# Sensors.net
KiCad netlist of a schematic drawn in Altium Designer
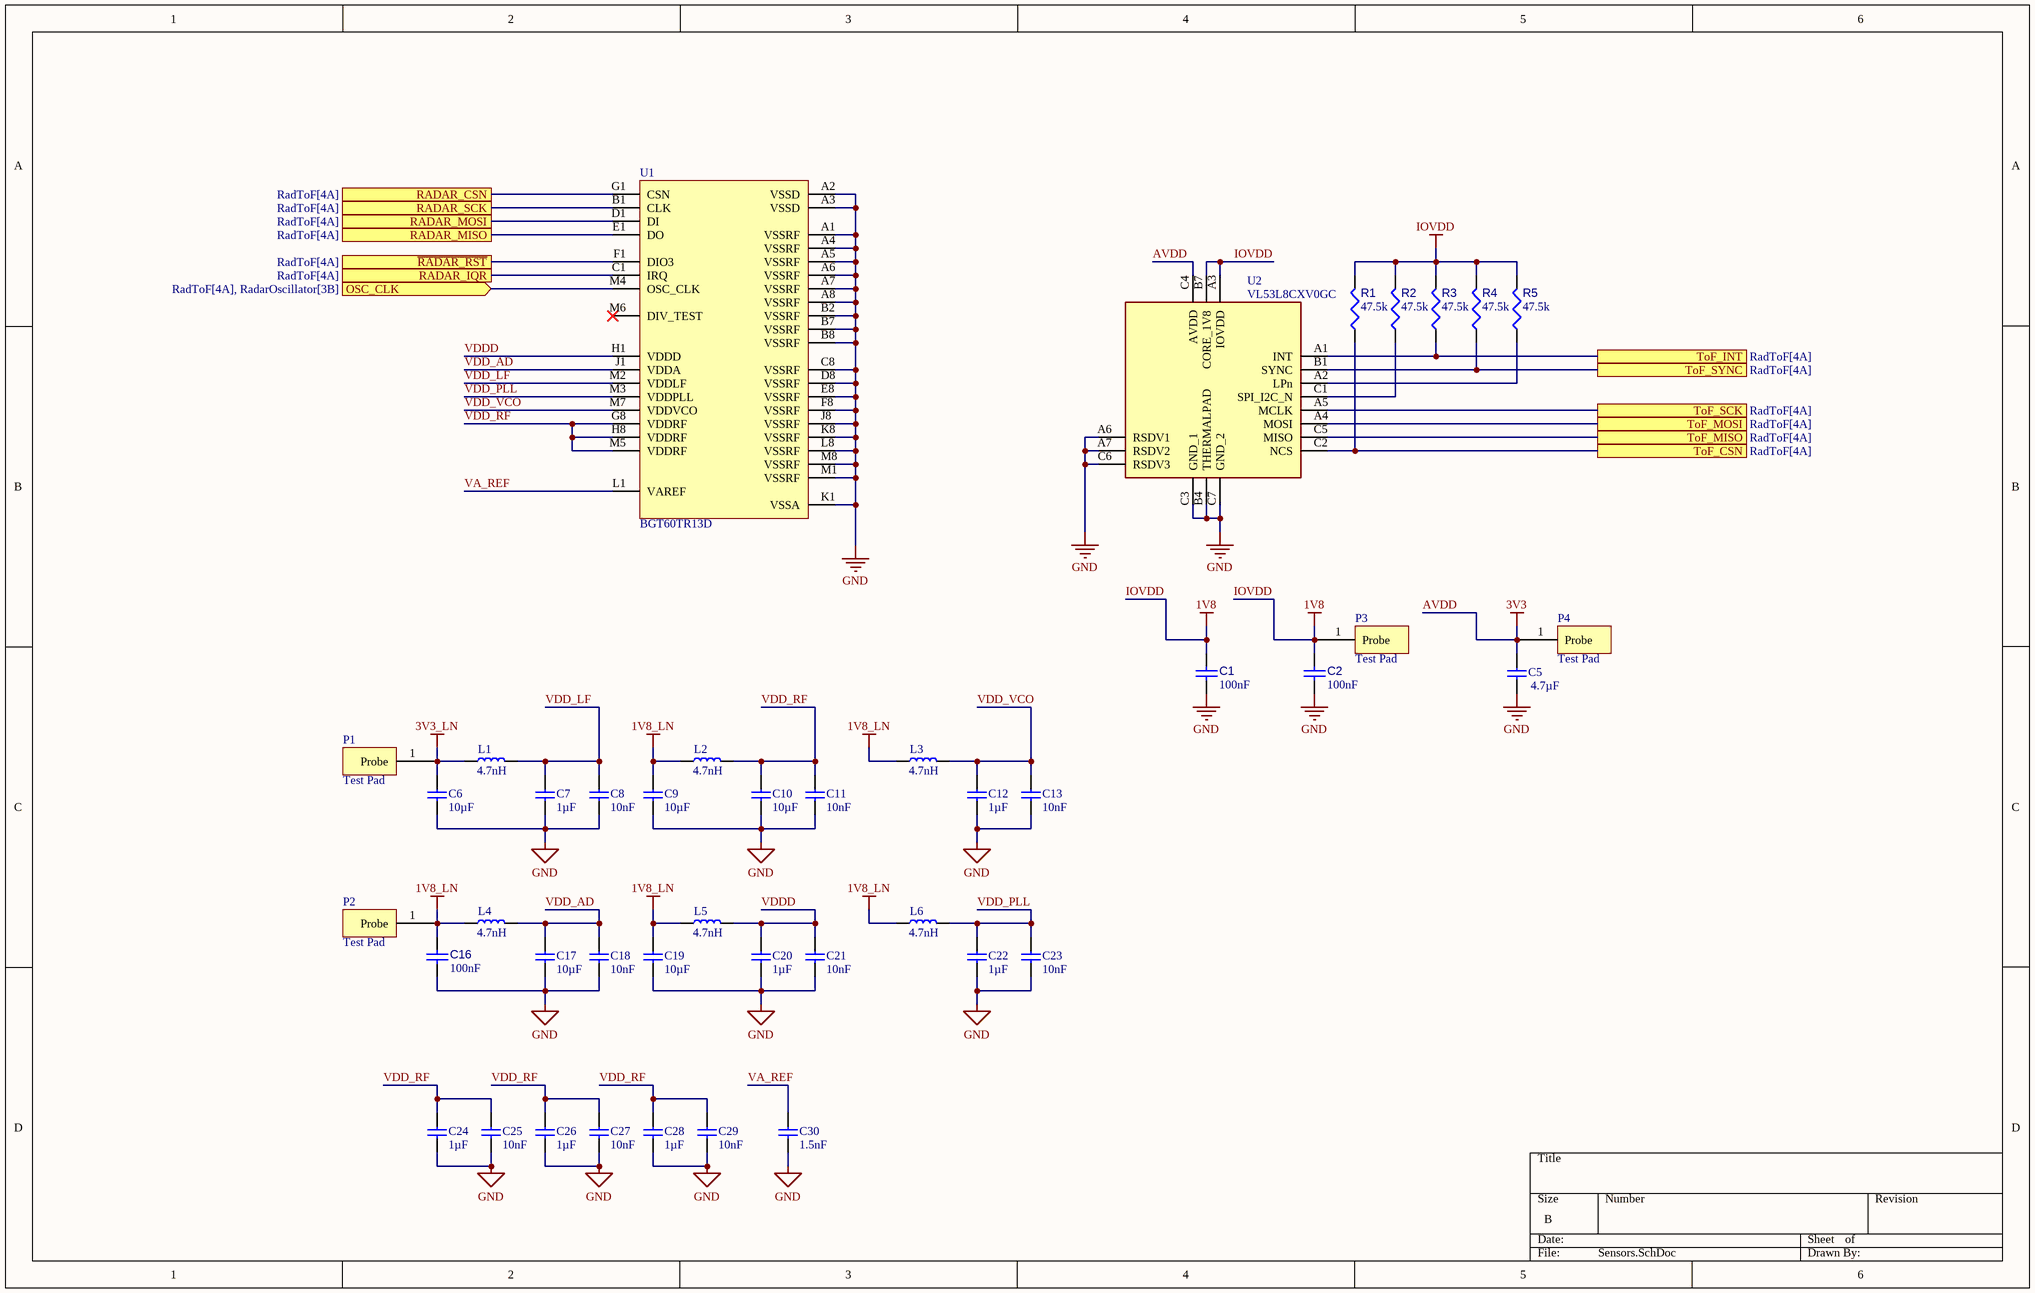
[diagram p0: Sensors.SchDoc]

(export (version "E")
  (design (tool "Eeschema 10.0.6"))
  (components
    (comp (ref "C1")
      (value "100nF")
      (footprint "CAPC0402(1005)60_L")
      (description "Chip Capacitor, 100nF +/-20%, 50V, 0402, Thickness 0.6 mm")
      (fields (field (name "TOLERANCE") "10%") (field (name "Comment") "Capacitor 100nF +/-20% 50V 0402"))
      (libsource (lib "Patrick Hupertz") (part "CAP-NP-2"))
    )
    (comp (ref "C2")
      (value "100nF")
      (footprint "CAPC0402(1005)60_L")
      (description "Chip Capacitor, 100nF +/-20%, 50V, 0402, Thickness 0.6 mm")
      (fields (field (name "TOLERANCE") "10%") (field (name "Comment") "Capacitor 100nF +/-20% 50V 0402"))
      (libsource (lib "Patrick Hupertz") (part "CAP-NP-2"))
    )
    (comp (ref "C5")
      (value "4.7µF")
      (footprint "CAP0201")
      (description "CAP CER  4.7uF 6.3V X5R 0201")
      (fields
        (field (name "TOLERANCE") "20%")
        (field (name "MANUFACTURER PART NUMBER") "GRM035R60J475ME15D")
        (field (name "SOURCE") "schuluka.SchLib")
      )
      (libsource (lib "Patrick Hupertz") (part "C_GRT033C80J224KE01D"))
    )
    (comp (ref "C6")
      (value "10µF")
      (footprint "CAP0402")
      (description "CAP CER  10uF 10V X5R 20% 0402")
      (fields
        (field (name "MANUFACTURER") "Murata Electronics")
        (field (name "TOLERANCE") "5%")
        (field (name "SOURCE") "schuluka.SchLib")
      )
      (libsource (lib "Patrick Hupertz") (part "C_GRT033C80J224KE01D"))
    )
    (comp (ref "C7")
      (value "1µF")
      (footprint "CAP0402")
      (description "CAP CER 1uF 25V X5R 0402")
      (fields
        (field (name "MANUFACTURER PART NUMBER") "GRM033R61A105ME15D")
        (field (name "MANUFACTURER") "Murata")
        (field (name "SOURCE") "schuluka.SchLib")
      )
      (libsource (lib "Patrick Hupertz") (part "C_GRT033C80J224KE01D"))
    )
    (comp (ref "C8")
      (value "10nF")
      (footprint "CAP0201")
      (description "CAP CER 10nF 6.3V X7R 0201")
      (fields
        (field (name "MANUFACTURER") "Murata Electronics")
        (field (name "TOLERANCE") "5%")
        (field (name "SOURCE") "schuluka.SchLib")
      )
      (libsource (lib "Patrick Hupertz") (part "C_GRT033C80J224KE01D"))
    )
    (comp (ref "C9")
      (value "10µF")
      (footprint "CAP0402")
      (description "CAP CER  10uF 10V X5R 20% 0402")
      (fields
        (field (name "MANUFACTURER") "Murata Electronics")
        (field (name "TOLERANCE") "5%")
        (field (name "SOURCE") "schuluka.SchLib")
      )
      (libsource (lib "Patrick Hupertz") (part "C_GRT033C80J224KE01D"))
    )
    (comp (ref "C10")
      (value "10µF")
      (footprint "CAP0402")
      (description "CAP CER  10uF 10V X5R 20% 0402")
      (fields
        (field (name "MANUFACTURER") "Murata Electronics")
        (field (name "TOLERANCE") "5%")
        (field (name "SOURCE") "schuluka.SchLib")
      )
      (libsource (lib "Patrick Hupertz") (part "C_GRT033C80J224KE01D"))
    )
    (comp (ref "C11")
      (value "10nF")
      (footprint "CAP0201")
      (description "CAP CER 10nF 6.3V X7R 0201")
      (fields
        (field (name "MANUFACTURER") "Murata Electronics")
        (field (name "TOLERANCE") "5%")
        (field (name "SOURCE") "schuluka.SchLib")
      )
      (libsource (lib "Patrick Hupertz") (part "C_GRT033C80J224KE01D"))
    )
    (comp (ref "C12")
      (value "1µF")
      (footprint "CAP0402")
      (description "CAP CER 1uF 25V X5R 0402")
      (fields
        (field (name "MANUFACTURER PART NUMBER") "GRM033R61A105ME15D")
        (field (name "MANUFACTURER") "Murata")
        (field (name "SOURCE") "schuluka.SchLib")
      )
      (libsource (lib "Patrick Hupertz") (part "C_GRT033C80J224KE01D"))
    )
    (comp (ref "C13")
      (value "10nF")
      (footprint "CAP0201")
      (description "CAP CER 10nF 6.3V X7R 0201")
      (fields
        (field (name "MANUFACTURER") "Murata Electronics")
        (field (name "TOLERANCE") "5%")
        (field (name "SOURCE") "schuluka.SchLib")
      )
      (libsource (lib "Patrick Hupertz") (part "C_GRT033C80J224KE01D"))
    )
    (comp (ref "C16")
      (value "100nF")
      (footprint "CAPC0402(1005)60_L")
      (description "Chip Capacitor, 100nF +/-20%, 50V, 0402, Thickness 0.6 mm")
      (fields (field (name "TOLERANCE") "10%") (field (name "Comment") "Capacitor 100nF +/-20% 50V 0402"))
      (libsource (lib "Patrick Hupertz") (part "CAP-NP-2"))
    )
    (comp (ref "C17")
      (value "10µF")
      (footprint "CAP0402")
      (description "CAP CER  10uF 10V X5R 20% 0402")
      (fields
        (field (name "MANUFACTURER") "Murata Electronics")
        (field (name "TOLERANCE") "5%")
        (field (name "SOURCE") "schuluka.SchLib")
      )
      (libsource (lib "Patrick Hupertz") (part "C_GRT033C80J224KE01D"))
    )
    (comp (ref "C18")
      (value "10nF")
      (footprint "CAP0201")
      (description "CAP CER 10nF 6.3V X7R 0201")
      (fields
        (field (name "MANUFACTURER") "Murata Electronics")
        (field (name "TOLERANCE") "5%")
        (field (name "SOURCE") "schuluka.SchLib")
      )
      (libsource (lib "Patrick Hupertz") (part "C_GRT033C80J224KE01D"))
    )
    (comp (ref "C19")
      (value "10µF")
      (footprint "CAP0402")
      (description "CAP CER  10uF 10V X5R 20% 0402")
      (fields
        (field (name "MANUFACTURER") "Murata Electronics")
        (field (name "TOLERANCE") "5%")
        (field (name "SOURCE") "schuluka.SchLib")
      )
      (libsource (lib "Patrick Hupertz") (part "C_GRT033C80J224KE01D"))
    )
    (comp (ref "C20")
      (value "1µF")
      (footprint "CAP0402")
      (description "CAP CER 1uF 25V X5R 0402")
      (fields
        (field (name "MANUFACTURER PART NUMBER") "GRM033R61A105ME15D")
        (field (name "MANUFACTURER") "Murata")
        (field (name "SOURCE") "schuluka.SchLib")
      )
      (libsource (lib "Patrick Hupertz") (part "C_GRT033C80J224KE01D"))
    )
    (comp (ref "C21")
      (value "10nF")
      (footprint "CAP0201")
      (description "CAP CER 10nF 6.3V X7R 0201")
      (fields
        (field (name "MANUFACTURER") "Murata Electronics")
        (field (name "TOLERANCE") "5%")
        (field (name "SOURCE") "schuluka.SchLib")
      )
      (libsource (lib "Patrick Hupertz") (part "C_GRT033C80J224KE01D"))
    )
    (comp (ref "C22")
      (value "1µF")
      (footprint "CAP0402")
      (description "CAP CER 1uF 25V X5R 0402")
      (fields
        (field (name "MANUFACTURER PART NUMBER") "GRM033R61A105ME15D")
        (field (name "MANUFACTURER") "Murata")
        (field (name "SOURCE") "schuluka.SchLib")
      )
      (libsource (lib "Patrick Hupertz") (part "C_GRT033C80J224KE01D"))
    )
    (comp (ref "C23")
      (value "10nF")
      (footprint "CAP0201")
      (description "CAP CER 10nF 6.3V X7R 0201")
      (fields
        (field (name "MANUFACTURER") "Murata Electronics")
        (field (name "TOLERANCE") "5%")
        (field (name "SOURCE") "schuluka.SchLib")
      )
      (libsource (lib "Patrick Hupertz") (part "C_GRT033C80J224KE01D"))
    )
    (comp (ref "C24")
      (value "1µF")
      (footprint "CAP0402")
      (description "CAP CER 1uF 25V X5R 0402")
      (fields
        (field (name "MANUFACTURER PART NUMBER") "GRM033R61A105ME15D")
        (field (name "MANUFACTURER") "Murata")
        (field (name "SOURCE") "schuluka.SchLib")
      )
      (libsource (lib "Patrick Hupertz") (part "C_GRT033C80J224KE01D"))
    )
    (comp (ref "C25")
      (value "10nF")
      (footprint "CAP0201")
      (description "CAP CER 10nF 6.3V X7R 0201")
      (fields
        (field (name "MANUFACTURER") "Murata Electronics")
        (field (name "TOLERANCE") "5%")
        (field (name "SOURCE") "schuluka.SchLib")
      )
      (libsource (lib "Patrick Hupertz") (part "C_GRT033C80J224KE01D"))
    )
    (comp (ref "C26")
      (value "1µF")
      (footprint "CAP0402")
      (description "CAP CER 1uF 25V X5R 0402")
      (fields
        (field (name "MANUFACTURER PART NUMBER") "GRM033R61A105ME15D")
        (field (name "MANUFACTURER") "Murata")
        (field (name "SOURCE") "schuluka.SchLib")
      )
      (libsource (lib "Patrick Hupertz") (part "C_GRT033C80J224KE01D"))
    )
    (comp (ref "C27")
      (value "10nF")
      (footprint "CAP0201")
      (description "CAP CER 10nF 6.3V X7R 0201")
      (fields
        (field (name "MANUFACTURER") "Murata Electronics")
        (field (name "TOLERANCE") "5%")
        (field (name "SOURCE") "schuluka.SchLib")
      )
      (libsource (lib "Patrick Hupertz") (part "C_GRT033C80J224KE01D"))
    )
    (comp (ref "C28")
      (value "1µF")
      (footprint "CAP0402")
      (description "CAP CER 1uF 25V X5R 0402")
      (fields
        (field (name "MANUFACTURER PART NUMBER") "GRM033R61A105ME15D")
        (field (name "MANUFACTURER") "Murata")
        (field (name "SOURCE") "schuluka.SchLib")
      )
      (libsource (lib "Patrick Hupertz") (part "C_GRT033C80J224KE01D"))
    )
    (comp (ref "C29")
      (value "10nF")
      (footprint "CAP0201")
      (description "CAP CER 10nF 6.3V X7R 0201")
      (fields
        (field (name "MANUFACTURER") "Murata Electronics")
        (field (name "TOLERANCE") "5%")
        (field (name "SOURCE") "schuluka.SchLib")
      )
      (libsource (lib "Patrick Hupertz") (part "C_GRT033C80J224KE01D"))
    )
    (comp (ref "C30")
      (value "1.5nF")
      (footprint "CAP0402")
      (description "CAP CER 1.5nF 50V X7R 0402")
      (fields
        (field (name "TOLERANCE") "5%")
        (field (name "MANUFACTURER PART NUMBER") "GRM155R71H103KA88D")
        (field (name "SOURCE") "schuluka.SchLib")
      )
      (libsource (lib "Patrick Hupertz") (part "C_GRT033C80J224KE01D"))
    )
    (comp (ref "L1")
      (value "4.7nH")
      (footprint "IND0402")
      (description "IND 4.7nH 800mA 110 mOHM 0402")
      (fields
        (field (name "PART NUMBER") "LQW15AN22NJ8ZD")
        (field (name "MANUFACTURER PART NUMBER") "LQG15WH2N2B02D")
        (field (name "SOURCE") "schuluka.SchLib")
      )
      (libsource (lib "Patrick Hupertz") (part "L_DFE252012F-1R0M"))
    )
    (comp (ref "L2")
      (value "4.7nH")
      (footprint "IND0402")
      (description "IND 4.7nH 800mA 110 mOHM 0402")
      (fields
        (field (name "PART NUMBER") "LQW15AN22NJ8ZD")
        (field (name "MANUFACTURER PART NUMBER") "LQG15WH2N2B02D")
        (field (name "SOURCE") "schuluka.SchLib")
      )
      (libsource (lib "Patrick Hupertz") (part "L_DFE252012F-1R0M"))
    )
    (comp (ref "L3")
      (value "4.7nH")
      (footprint "IND0402")
      (description "IND 4.7nH 800mA 110 mOHM 0402")
      (fields
        (field (name "PART NUMBER") "LQW15AN22NJ8ZD")
        (field (name "MANUFACTURER PART NUMBER") "LQG15WH2N2B02D")
        (field (name "SOURCE") "schuluka.SchLib")
      )
      (libsource (lib "Patrick Hupertz") (part "L_DFE252012F-1R0M"))
    )
    (comp (ref "L4")
      (value "4.7nH")
      (footprint "IND0402")
      (description "IND 4.7nH 800mA 110 mOHM 0402")
      (fields
        (field (name "PART NUMBER") "LQW15AN22NJ8ZD")
        (field (name "MANUFACTURER PART NUMBER") "LQG15WH2N2B02D")
        (field (name "SOURCE") "schuluka.SchLib")
      )
      (libsource (lib "Patrick Hupertz") (part "L_DFE252012F-1R0M"))
    )
    (comp (ref "L5")
      (value "4.7nH")
      (footprint "IND0402")
      (description "IND 4.7nH 800mA 110 mOHM 0402")
      (fields
        (field (name "PART NUMBER") "LQW15AN22NJ8ZD")
        (field (name "MANUFACTURER PART NUMBER") "LQG15WH2N2B02D")
        (field (name "SOURCE") "schuluka.SchLib")
      )
      (libsource (lib "Patrick Hupertz") (part "L_DFE252012F-1R0M"))
    )
    (comp (ref "L6")
      (value "4.7nH")
      (footprint "IND0402")
      (description "IND 4.7nH 800mA 110 mOHM 0402")
      (fields
        (field (name "PART NUMBER") "LQW15AN22NJ8ZD")
        (field (name "MANUFACTURER PART NUMBER") "LQG15WH2N2B02D")
        (field (name "SOURCE") "schuluka.SchLib")
      )
      (libsource (lib "Patrick Hupertz") (part "L_DFE252012F-1R0M"))
    )
    (comp (ref "P1") (value "Test Pad") (footprint "test pad") (libsource (lib "SchlibPH") (part "Test Pad")))
    (comp (ref "P2") (value "Test Pad") (footprint "test pad") (libsource (lib "SchlibPH") (part "Test Pad")))
    (comp (ref "P3") (value "Test Pad") (footprint "test pad") (libsource (lib "") (part "Test Pad_1")))
    (comp (ref "P4") (value "Test Pad") (footprint "test pad") (libsource (lib "") (part "Test Pad_1")))
    (comp (ref "R1")
      (value "47.5k")
      (footprint "RESC0402(1005)_L")
      (description "Chip Resistor, 47,5 kOhms, +/-1 %, 63 mW, -55 to 155 degC, 0402")
      (fields (field (name "POWER") "63mW") (field (name "TOLERANCE") "1%"))
      (libsource (lib "Patrick Hupertz") (part "RES-2"))
    )
    (comp (ref "R2")
      (value "47.5k")
      (footprint "RESC0402(1005)_L")
      (description "Chip Resistor, 47,5 kOhms, +/-1 %, 63 mW, -55 to 155 degC, 0402")
      (fields (field (name "POWER") "63mW") (field (name "TOLERANCE") "1%"))
      (libsource (lib "Patrick Hupertz") (part "RES-2"))
    )
    (comp (ref "R3")
      (value "47.5k")
      (footprint "RESC0402(1005)_L")
      (description "Chip Resistor, 47,5 kOhms, +/-1 %, 63 mW, -55 to 155 degC, 0402")
      (fields (field (name "POWER") "63mW") (field (name "TOLERANCE") "1%"))
      (libsource (lib "Patrick Hupertz") (part "RES-2"))
    )
    (comp (ref "R4")
      (value "47.5k")
      (footprint "RESC0402(1005)_L")
      (description "Chip Resistor, 47,5 kOhms, +/-1 %, 63 mW, -55 to 155 degC, 0402")
      (fields (field (name "POWER") "63mW") (field (name "TOLERANCE") "1%"))
      (libsource (lib "Patrick Hupertz") (part "RES-2"))
    )
    (comp (ref "R5")
      (value "47.5k")
      (footprint "RESC0402(1005)_L")
      (description "Chip Resistor, 47,5 kOhms, +/-1 %, 63 mW, -55 to 155 degC, 0402")
      (fields (field (name "POWER") "63mW") (field (name "TOLERANCE") "1%"))
      (libsource (lib "Patrick Hupertz") (part "RES-2"))
    )
    (comp (ref "U1")
      (value "BGT60TR13D")
      (footprint "BGT60TR13D")
      (description "XENSIV 60 GHz radar system platform")
      (fields
        (field (name "MANUFACTURER") "Infineon Technologies")
        (field (name "MANUFACTURER PART NUMBER") "BGT61TR13C")
      )
      (libsource (lib "SchlibPH") (part "SENS_BGT60TR13D"))
    )
    (comp (ref "U2")
      (value "VL53L8CXV0GC")
      (footprint "VL53L8CXV0GC1")
      (description "Low-power high-performance 8x8 multizone Time-of-Flight sensor 940 nm, 6.4x3.0x1.75 mm, -30 to 85C")
      (fields
        (field (name "MANUFACTURER_PART_NUMBER") "VL53L8CXV0GC/1")
        (field (name "MOUSER PART NUMBER") "511-VL53L8CXV0GC/1")
      )
      (libsource (lib "SchlibPH") (part "VL53L8CXV0GC"))
    )
  )
  (nets
    (net (code "1") (name "/OSC_CLK") (class "Default")
      (node (ref "U1") (pin "M4") (pinfunction "OSC_CLK_M4") (pintype "passive"))
    )
    (net (code "2") (name "/RADAR_CSN") (class "Default")
      (node (ref "U1") (pin "G1") (pinfunction "CSN_G1") (pintype "passive"))
    )
    (net (code "3") (name "/RADAR_IQR") (class "Default")
      (node (ref "U1") (pin "C1") (pinfunction "IRQ_C1") (pintype "passive"))
    )
    (net (code "4") (name "/RADAR_MISO") (class "Default")
      (node (ref "U1") (pin "E1") (pinfunction "DO_E1") (pintype "passive"))
    )
    (net (code "5") (name "/RADAR_MOSI") (class "Default")
      (node (ref "U1") (pin "D1") (pinfunction "DI_D1") (pintype "passive"))
    )
    (net (code "6") (name "/RADAR_SCK") (class "Default")
      (node (ref "U1") (pin "B1") (pinfunction "CLK_B1") (pintype "passive"))
    )
    (net (code "7") (name "/ToF_CSN") (class "Default")
      (node (ref "R1") (pin "1") (pinfunction "1_1") (pintype "passive"))
      (node (ref "U2") (pin "C2") (pinfunction "NCS_C2") (pintype "passive"))
    )
    (net (code "8") (name "/ToF_INT") (class "Default")
      (node (ref "R3") (pin "1") (pinfunction "1_1") (pintype "passive"))
      (node (ref "U2") (pin "A1") (pinfunction "INT_A1") (pintype "passive"))
    )
    (net (code "9") (name "/ToF_MISO") (class "Default")
      (node (ref "U2") (pin "C5") (pinfunction "MISO_C5") (pintype "passive"))
    )
    (net (code "10") (name "/ToF_MOSI") (class "Default")
      (node (ref "U2") (pin "A4") (pinfunction "MOSI_A4") (pintype "passive"))
    )
    (net (code "11") (name "/ToF_SCK") (class "Default")
      (node (ref "U2") (pin "A5") (pinfunction "MCLK_A5") (pintype "passive"))
    )
    (net (code "12") (name "/ToF_SYNC") (class "Default")
      (node (ref "R4") (pin "1") (pinfunction "1_1") (pintype "passive"))
      (node (ref "U2") (pin "B1") (pinfunction "SYNC_B1") (pintype "passive"))
    )
    (net (code "13") (name "/VA_REF") (class "Default")
      (node (ref "C30") (pin "2") (pinfunction "2_2") (pintype "passive"))
      (node (ref "U1") (pin "L1") (pinfunction "VAREF_L1") (pintype "passive"))
    )
    (net (code "14") (name "/VDDD") (class "Default")
      (node (ref "C20") (pin "2") (pinfunction "2_2") (pintype "passive"))
      (node (ref "C21") (pin "2") (pinfunction "2_2") (pintype "passive"))
      (node (ref "L5") (pin "2") (pinfunction "2_2") (pintype "passive"))
      (node (ref "U1") (pin "H1") (pinfunction "VDDD_H1") (pintype "passive"))
    )
    (net (code "15") (name "/VDD_AD") (class "Default")
      (node (ref "C17") (pin "2") (pinfunction "2_2") (pintype "passive"))
      (node (ref "C18") (pin "2") (pinfunction "2_2") (pintype "passive"))
      (node (ref "L4") (pin "2") (pinfunction "2_2") (pintype "passive"))
      (node (ref "U1") (pin "J1") (pinfunction "VDDA_J1") (pintype "passive"))
    )
    (net (code "16") (name "/VDD_LF") (class "Default")
      (node (ref "C7") (pin "2") (pinfunction "2_2") (pintype "passive"))
      (node (ref "C8") (pin "2") (pinfunction "2_2") (pintype "passive"))
      (node (ref "L1") (pin "2") (pinfunction "2_2") (pintype "passive"))
      (node (ref "U1") (pin "M2") (pinfunction "VDDLF_M2") (pintype "passive"))
    )
    (net (code "17") (name "/VDD_PLL") (class "Default")
      (node (ref "C22") (pin "2") (pinfunction "2_2") (pintype "passive"))
      (node (ref "C23") (pin "2") (pinfunction "2_2") (pintype "passive"))
      (node (ref "L6") (pin "2") (pinfunction "2_2") (pintype "passive"))
      (node (ref "U1") (pin "M3") (pinfunction "VDDPLL_M3") (pintype "passive"))
    )
    (net (code "18") (name "/VDD_RF") (class "Default")
      (node (ref "C10") (pin "2") (pinfunction "2_2") (pintype "passive"))
      (node (ref "C11") (pin "2") (pinfunction "2_2") (pintype "passive"))
      (node (ref "C24") (pin "2") (pinfunction "2_2") (pintype "passive"))
      (node (ref "C25") (pin "2") (pinfunction "2_2") (pintype "passive"))
      (node (ref "C26") (pin "2") (pinfunction "2_2") (pintype "passive"))
      (node (ref "C27") (pin "2") (pinfunction "2_2") (pintype "passive"))
      (node (ref "C28") (pin "2") (pinfunction "2_2") (pintype "passive"))
      (node (ref "C29") (pin "2") (pinfunction "2_2") (pintype "passive"))
      (node (ref "L2") (pin "2") (pinfunction "2_2") (pintype "passive"))
      (node (ref "U1") (pin "G8") (pinfunction "VDDRF_G8") (pintype "passive"))
      (node (ref "U1") (pin "H8") (pinfunction "VDDRF_H8") (pintype "passive"))
      (node (ref "U1") (pin "M5") (pinfunction "VDDRF_M5") (pintype "passive"))
    )
    (net (code "19") (name "/VDD_VCO") (class "Default")
      (node (ref "C12") (pin "2") (pinfunction "2_2") (pintype "passive"))
      (node (ref "C13") (pin "2") (pinfunction "2_2") (pintype "passive"))
      (node (ref "L3") (pin "2") (pinfunction "2_2") (pintype "passive"))
      (node (ref "U1") (pin "M7") (pinfunction "VDDVCO_M7") (pintype "passive"))
    )
    (net (code "20") (name "/~{RADAR_RST}") (class "Default")
      (node (ref "U1") (pin "F1") (pinfunction "DIO3_F1") (pintype "passive"))
    )
    (net (code "21") (name "1V8") (class "Default")
      (node (ref "C1") (pin "1") (pinfunction "1_1") (pintype "passive"))
      (node (ref "C2") (pin "1") (pinfunction "1_1") (pintype "passive"))
      (node (ref "P3") (pin "1") (pinfunction "Probe_1") (pintype "passive"))
      (node (ref "R1") (pin "2") (pinfunction "2_2") (pintype "passive"))
      (node (ref "R2") (pin "2") (pinfunction "2_2") (pintype "passive"))
      (node (ref "R3") (pin "2") (pinfunction "2_2") (pintype "passive"))
      (node (ref "R4") (pin "2") (pinfunction "2_2") (pintype "passive"))
      (node (ref "R5") (pin "2") (pinfunction "2_2") (pintype "passive"))
      (node (ref "U2") (pin "A3") (pinfunction "IOVDD_A3") (pintype "passive"))
      (node (ref "U2") (pin "B7") (pinfunction "CORE_1V8_B7") (pintype "passive"))
    )
    (net (code "22") (name "1V8_LN") (class "Default")
      (node (ref "C16") (pin "1") (pinfunction "1_1") (pintype "passive"))
      (node (ref "C19") (pin "2") (pinfunction "2_2") (pintype "passive"))
      (node (ref "C9") (pin "2") (pinfunction "2_2") (pintype "passive"))
      (node (ref "L2") (pin "1") (pinfunction "1_1") (pintype "passive"))
      (node (ref "L3") (pin "1") (pinfunction "1_1") (pintype "passive"))
      (node (ref "L4") (pin "1") (pinfunction "1_1") (pintype "passive"))
      (node (ref "L5") (pin "1") (pinfunction "1_1") (pintype "passive"))
      (node (ref "L6") (pin "1") (pinfunction "1_1") (pintype "passive"))
      (node (ref "P2") (pin "1") (pinfunction "Probe_1") (pintype "passive"))
    )
    (net (code "23") (name "3V3") (class "Default")
      (node (ref "C5") (pin "2") (pinfunction "2_2") (pintype "passive"))
      (node (ref "P4") (pin "1") (pinfunction "Probe_1") (pintype "passive"))
      (node (ref "U2") (pin "C4") (pinfunction "AVDD_C4") (pintype "passive"))
    )
    (net (code "24") (name "3V3_LN") (class "Default")
      (node (ref "C6") (pin "2") (pinfunction "2_2") (pintype "passive"))
      (node (ref "L1") (pin "1") (pinfunction "1_1") (pintype "passive"))
      (node (ref "P1") (pin "1") (pinfunction "Probe_1") (pintype "passive"))
    )
    (net (code "25") (name "GND") (class "Default")
      (node (ref "C1") (pin "2") (pinfunction "2_2") (pintype "passive"))
      (node (ref "C10") (pin "1") (pinfunction "1_1") (pintype "passive"))
      (node (ref "C11") (pin "1") (pinfunction "1_1") (pintype "passive"))
      (node (ref "C12") (pin "1") (pinfunction "1_1") (pintype "passive"))
      (node (ref "C13") (pin "1") (pinfunction "1_1") (pintype "passive"))
      (node (ref "C16") (pin "2") (pinfunction "2_2") (pintype "passive"))
      (node (ref "C17") (pin "1") (pinfunction "1_1") (pintype "passive"))
      (node (ref "C18") (pin "1") (pinfunction "1_1") (pintype "passive"))
      (node (ref "C19") (pin "1") (pinfunction "1_1") (pintype "passive"))
      (node (ref "C2") (pin "2") (pinfunction "2_2") (pintype "passive"))
      (node (ref "C20") (pin "1") (pinfunction "1_1") (pintype "passive"))
      (node (ref "C21") (pin "1") (pinfunction "1_1") (pintype "passive"))
      (node (ref "C22") (pin "1") (pinfunction "1_1") (pintype "passive"))
      (node (ref "C23") (pin "1") (pinfunction "1_1") (pintype "passive"))
      (node (ref "C24") (pin "1") (pinfunction "1_1") (pintype "passive"))
      (node (ref "C25") (pin "1") (pinfunction "1_1") (pintype "passive"))
      (node (ref "C26") (pin "1") (pinfunction "1_1") (pintype "passive"))
      (node (ref "C27") (pin "1") (pinfunction "1_1") (pintype "passive"))
      (node (ref "C28") (pin "1") (pinfunction "1_1") (pintype "passive"))
      (node (ref "C29") (pin "1") (pinfunction "1_1") (pintype "passive"))
      (node (ref "C30") (pin "1") (pinfunction "1_1") (pintype "passive"))
      (node (ref "C5") (pin "1") (pinfunction "1_1") (pintype "passive"))
      (node (ref "C6") (pin "1") (pinfunction "1_1") (pintype "passive"))
      (node (ref "C7") (pin "1") (pinfunction "1_1") (pintype "passive"))
      (node (ref "C8") (pin "1") (pinfunction "1_1") (pintype "passive"))
      (node (ref "C9") (pin "1") (pinfunction "1_1") (pintype "passive"))
      (node (ref "U1") (pin "A1") (pinfunction "VSSRF_A1") (pintype "passive"))
      (node (ref "U1") (pin "A2") (pinfunction "VSSD_A2") (pintype "passive"))
      (node (ref "U1") (pin "A3") (pinfunction "VSSD_A3") (pintype "passive"))
      (node (ref "U1") (pin "A4") (pinfunction "VSSRF_A4") (pintype "passive"))
      (node (ref "U1") (pin "A5") (pinfunction "VSSRF_A5") (pintype "passive"))
      (node (ref "U1") (pin "A6") (pinfunction "VSSRF_A6") (pintype "passive"))
      (node (ref "U1") (pin "A7") (pinfunction "VSSRF_A7") (pintype "passive"))
      (node (ref "U1") (pin "A8") (pinfunction "VSSRF_A8") (pintype "passive"))
      (node (ref "U1") (pin "B2") (pinfunction "VSSRF_B2") (pintype "passive"))
      (node (ref "U1") (pin "B7") (pinfunction "VSSRF_B7") (pintype "passive"))
      (node (ref "U1") (pin "B8") (pinfunction "VSSRF_B8") (pintype "passive"))
      (node (ref "U1") (pin "C8") (pinfunction "VSSRF_C8") (pintype "passive"))
      (node (ref "U1") (pin "D8") (pinfunction "VSSRF_D8") (pintype "passive"))
      (node (ref "U1") (pin "E8") (pinfunction "VSSRF_E8") (pintype "passive"))
      (node (ref "U1") (pin "F8") (pinfunction "VSSRF_F8") (pintype "passive"))
      (node (ref "U1") (pin "J8") (pinfunction "VSSRF_J8") (pintype "passive"))
      (node (ref "U1") (pin "K1") (pinfunction "VSSA_K1") (pintype "passive"))
      (node (ref "U1") (pin "K8") (pinfunction "VSSRF_K8") (pintype "passive"))
      (node (ref "U1") (pin "L8") (pinfunction "VSSRF_L8") (pintype "passive"))
      (node (ref "U1") (pin "M1") (pinfunction "VSSRF_M1") (pintype "passive"))
      (node (ref "U1") (pin "M8") (pinfunction "VSSRF_M8") (pintype "passive"))
      (node (ref "U2") (pin "A6") (pinfunction "RSDV1_A6") (pintype "passive"))
      (node (ref "U2") (pin "A7") (pinfunction "RSDV2_A7") (pintype "passive"))
      (node (ref "U2") (pin "B4") (pinfunction "THERMALPAD_B4") (pintype "passive"))
      (node (ref "U2") (pin "C3") (pinfunction "GND_1_C3") (pintype "passive"))
      (node (ref "U2") (pin "C6") (pinfunction "RSDV3_C6") (pintype "passive"))
      (node (ref "U2") (pin "C7") (pinfunction "GND_2_C7") (pintype "passive"))
    )
    (net (code "26") (name "Net-(U2-LPn)") (class "Default")
      (node (ref "R5") (pin "1") (pinfunction "1_1") (pintype "passive"))
      (node (ref "U2") (pin "A2") (pinfunction "LPn_A2") (pintype "passive"))
    )
    (net (code "27") (name "Net-(U2-SPI_I2C_N)") (class "Default")
      (node (ref "R2") (pin "1") (pinfunction "1_1") (pintype "passive"))
      (node (ref "U2") (pin "C1") (pinfunction "SPI_I2C_N_C1") (pintype "passive"))
    )
    (net (code "28") (name "unconnected-(U1-DIV_TEST-PadM6)") (class "Default")
      (node (ref "U1") (pin "M6") (pinfunction "DIV_TEST_M6") (pintype "passive+no_connect"))
    )
  )
)
